# tick-ds3231-breakout-mk-2_1.net
KiCad netlist of a schematic drawn in EAGLE
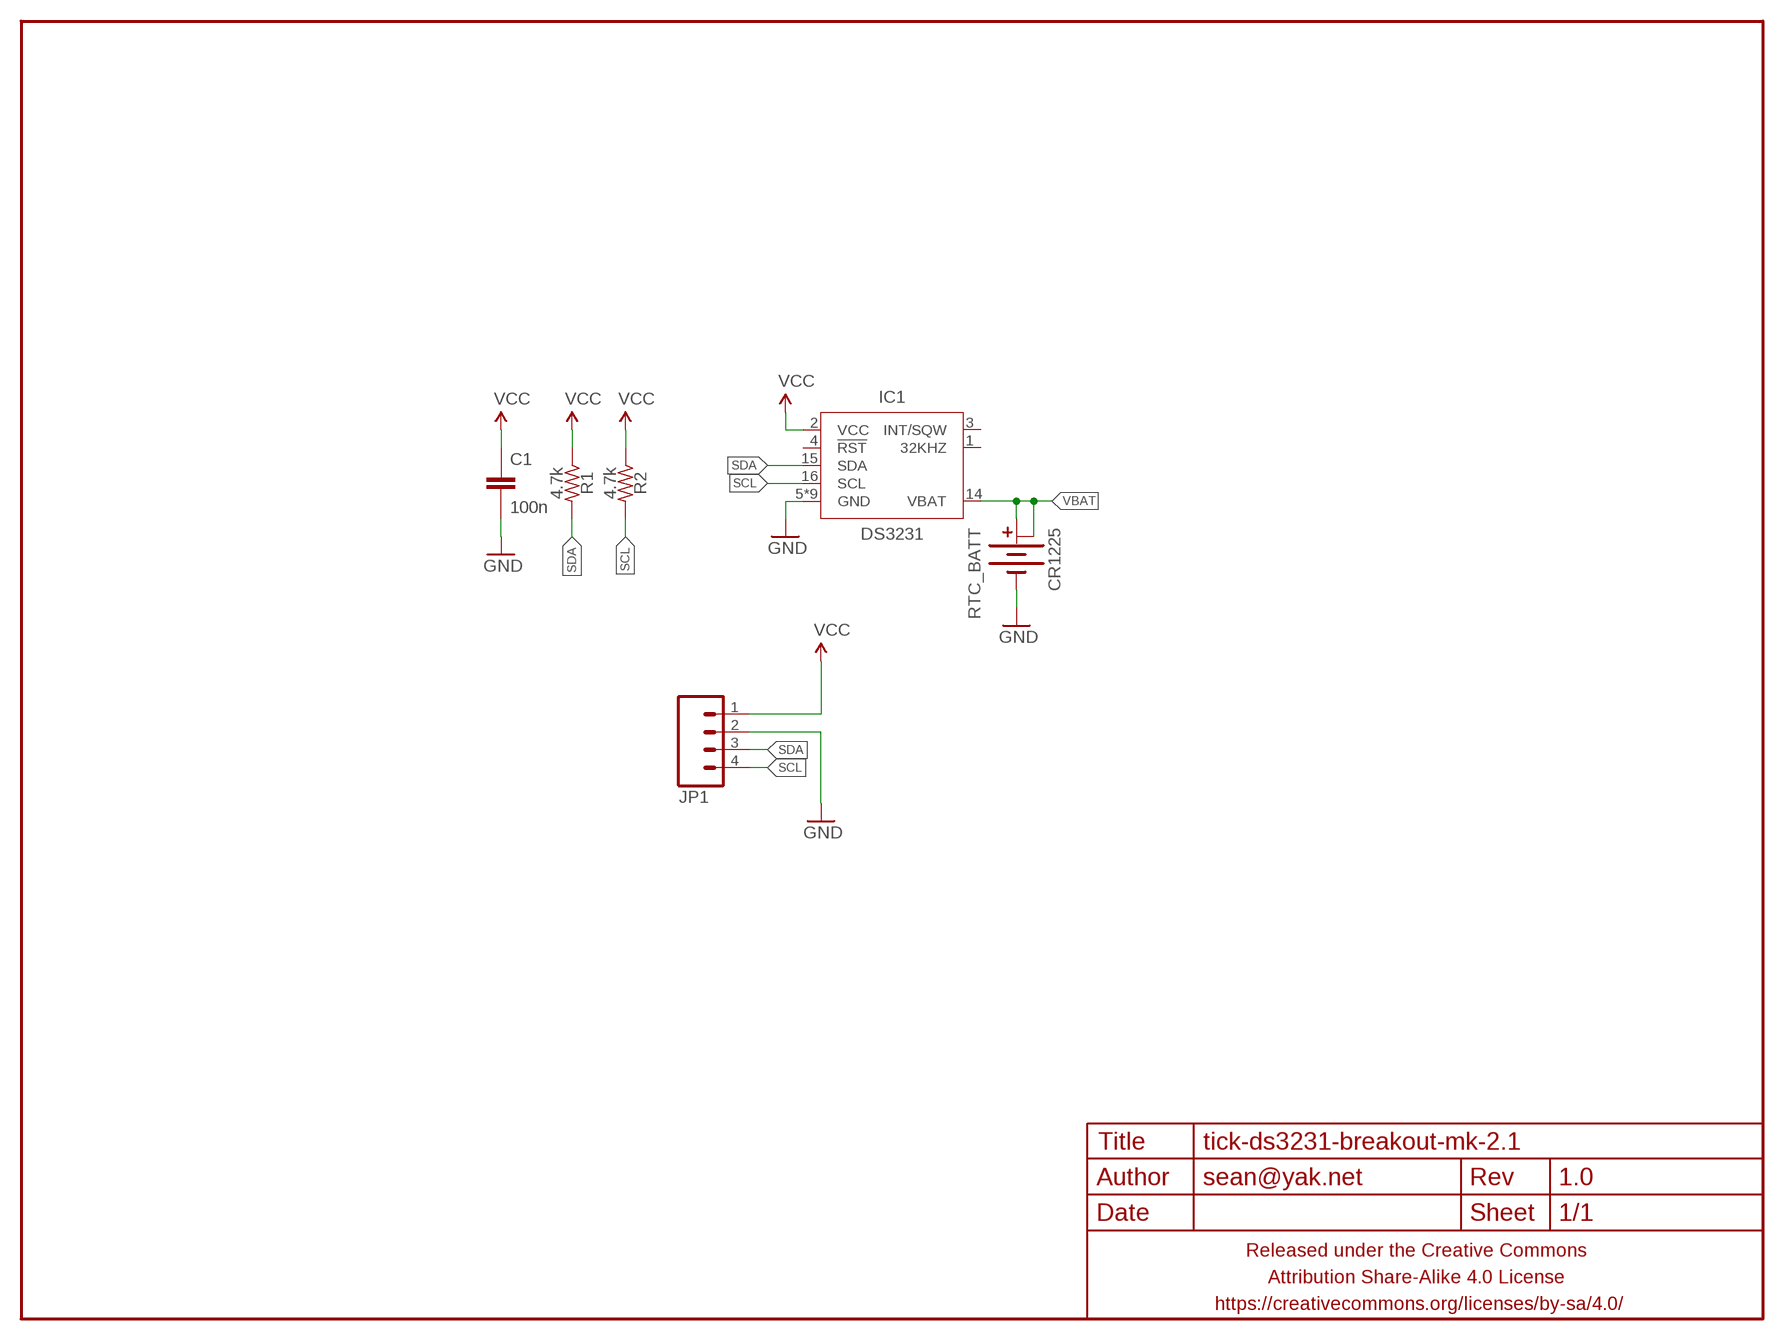
[diagram p0: schematic, sheet 1]

(export (version "E")
  (design (tool "Eeschema 10.0.6"))
  (components
    (comp (ref "C1")
      (value "100n")
      (footprint "eagle-import:C0805")
      (libsource (lib "eagle-import") (part "CAPACITOR-CERAMICC0805"))
    )
    (comp (ref "FRAME1")
      (value "FRAME-LETTERNO_PACKAGE")
      (footprint "eagle-import:DUMMY")
      (fields (field (name "DESIGNER") "sean@yak.net") (field (name "VERSION") "1.0"))
      (libsource (lib "eagle-import") (part "FRAME-LETTERNO_PACKAGE"))
    )
    (comp (ref "IC1")
      (value "DS3231")
      (footprint "eagle-import:SO16W")
      (libsource (lib "eagle-import") (part "DS3231"))
    )
    (comp (ref "JP1")
      (value "M04PTH")
      (footprint "eagle-import:1X04-PTH-VERT")
      (libsource (lib "eagle-import") (part "M04PTH"))
    )
    (comp (ref "R1")
      (value "4.7k")
      (footprint "eagle-import:R0805")
      (libsource (lib "eagle-import") (part "RESISTORR0805"))
    )
    (comp (ref "R2")
      (value "4.7k")
      (footprint "eagle-import:R0805")
      (libsource (lib "eagle-import") (part "RESISTORR0805"))
    )
    (comp (ref "RTC_BATT")
      (value "CR1225")
      (footprint "eagle-import:BATTCON_12MM_SMD")
      (libsource (lib "eagle-import") (part "BATTERY-COINCR1225_SMD_SMALLER"))
    )
  )
  (nets
    (net (code "1") (name "GND") (class "Default")
      (node (ref "C1") (pin "2") (pinfunction "2_2") (pintype "passive"))
      (node (ref "IC1") (pin "10") (pinfunction "GND_10") (pintype "bidirectional"))
      (node (ref "IC1") (pin "11") (pinfunction "GND_11") (pintype "bidirectional"))
      (node (ref "IC1") (pin "12") (pinfunction "GND_12") (pintype "bidirectional"))
      (node (ref "IC1") (pin "13") (pinfunction "GND_13") (pintype "bidirectional"))
      (node (ref "IC1") (pin "5") (pinfunction "GND_5") (pintype "bidirectional"))
      (node (ref "IC1") (pin "6") (pinfunction "GND_6") (pintype "bidirectional"))
      (node (ref "IC1") (pin "7") (pinfunction "GND_7") (pintype "bidirectional"))
      (node (ref "IC1") (pin "8") (pinfunction "GND_8") (pintype "bidirectional"))
      (node (ref "IC1") (pin "9") (pinfunction "GND_9") (pintype "bidirectional"))
      (node (ref "JP1") (pin "2") (pinfunction "2_2") (pintype "passive"))
      (node (ref "RTC_BATT") (pin "-") (pinfunction "-_-") (pintype "bidirectional"))
    )
    (net (code "2") (name "SCL") (class "Default")
      (node (ref "IC1") (pin "16") (pinfunction "SCL_16") (pintype "bidirectional"))
      (node (ref "JP1") (pin "4") (pinfunction "4_4") (pintype "passive"))
      (node (ref "R2") (pin "2") (pinfunction "2_2") (pintype "passive"))
    )
    (net (code "3") (name "SDA") (class "Default")
      (node (ref "IC1") (pin "15") (pinfunction "SDA_15") (pintype "bidirectional"))
      (node (ref "JP1") (pin "3") (pinfunction "3_3") (pintype "passive"))
      (node (ref "R1") (pin "2") (pinfunction "2_2") (pintype "passive"))
    )
    (net (code "4") (name "VBAT") (class "Default")
      (node (ref "IC1") (pin "14") (pinfunction "VBAT_14") (pintype "bidirectional"))
      (node (ref "RTC_BATT") (pin "+@1") (pinfunction "+_+@1") (pintype "bidirectional"))
      (node (ref "RTC_BATT") (pin "+@2") (pinfunction "+1_+@2") (pintype "bidirectional"))
    )
    (net (code "5") (name "VCC") (class "Default")
      (node (ref "C1") (pin "1") (pinfunction "1_1") (pintype "passive"))
      (node (ref "IC1") (pin "2") (pinfunction "VCC_2") (pintype "bidirectional"))
      (node (ref "JP1") (pin "1") (pinfunction "1_1") (pintype "passive"))
      (node (ref "R1") (pin "1") (pinfunction "1_1") (pintype "passive"))
      (node (ref "R2") (pin "1") (pinfunction "1_1") (pintype "passive"))
    )
    (net (code "6") (name "unconnected-(IC1-32KHZ-Pad1)") (class "Default")
      (node (ref "IC1") (pin "1") (pinfunction "32KHZ_1") (pintype "bidirectional"))
    )
    (net (code "7") (name "unconnected-(IC1-INT{slash}SQW-Pad3)") (class "Default")
      (node (ref "IC1") (pin "3") (pinfunction "INT/SQW_3") (pintype "bidirectional"))
    )
    (net (code "8") (name "unconnected-(IC1-~{RST}-Pad4)") (class "Default")
      (node (ref "IC1") (pin "4") (pinfunction "~{RST}_4") (pintype "bidirectional"))
    )
  )
)
